# MAIN.net
KiCad netlist of a schematic drawn in Altium Designer
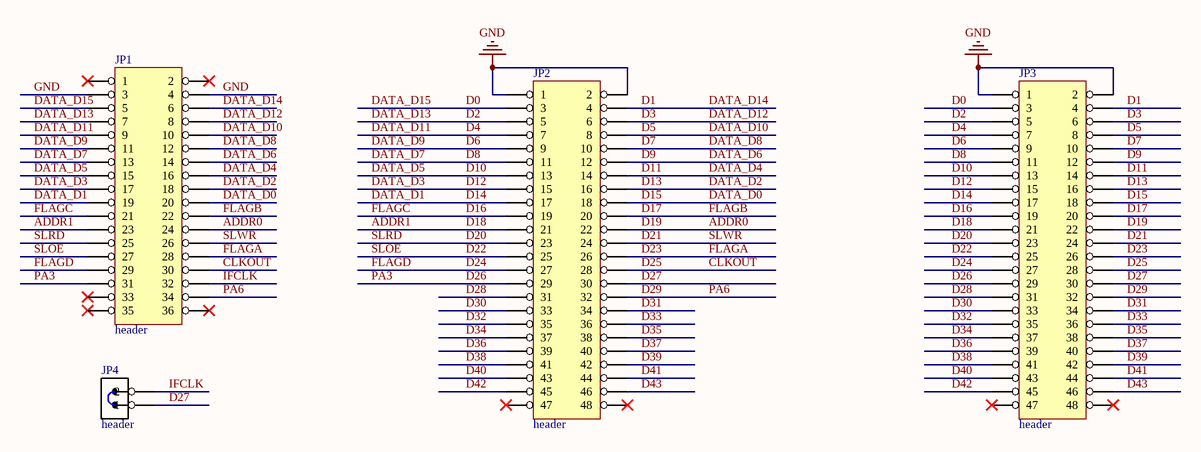
[diagram p0: MAIN.SchDoc]

(export (version "E")
  (design (tool "Eeschema 10.0.6"))
  (components
    (comp (ref "JP1")
      (value "header")
      (footprint "header2X18")
      (libsource (lib "My Footprint") (part "HEADER 18X2"))
    )
    (comp (ref "JP2")
      (value "header")
      (footprint "header2X24")
      (libsource (lib "My Footprint") (part "HEADER 24X2"))
    )
    (comp (ref "JP3")
      (value "header")
      (footprint "header2X24")
      (libsource (lib "My Footprint") (part "HEADER 24X2"))
    )
    (comp (ref "JP4")
      (value "header")
      (footprint "header2")
      (libsource (lib "My Footprint") (part "HEADER 2"))
    )
  )
  (nets
    (net (code "1") (name "/ADDR0") (class "Default")
      (node (ref "JP1") (pin "24") (pinfunction "24_24") (pintype "passive"))
      (node (ref "JP2") (pin "22") (pinfunction "22_22") (pintype "passive"))
      (node (ref "JP3") (pin "22") (pinfunction "22_22") (pintype "passive"))
    )
    (net (code "2") (name "/ADDR1") (class "Default")
      (node (ref "JP1") (pin "23") (pinfunction "23_23") (pintype "passive"))
      (node (ref "JP2") (pin "21") (pinfunction "21_21") (pintype "passive"))
      (node (ref "JP3") (pin "21") (pinfunction "21_21") (pintype "passive"))
    )
    (net (code "3") (name "/CLKOUT") (class "Default")
      (node (ref "JP1") (pin "30") (pinfunction "30_30") (pintype "passive"))
      (node (ref "JP2") (pin "28") (pinfunction "28_28") (pintype "passive"))
      (node (ref "JP3") (pin "28") (pinfunction "28_28") (pintype "passive"))
    )
    (net (code "4") (name "/D0") (class "Default")
      (node (ref "JP1") (pin "5") (pinfunction "5_5") (pintype "passive"))
      (node (ref "JP2") (pin "3") (pinfunction "3_3") (pintype "passive"))
      (node (ref "JP3") (pin "3") (pinfunction "3_3") (pintype "passive"))
    )
    (net (code "5") (name "/D1") (class "Default")
      (node (ref "JP1") (pin "6") (pinfunction "6_6") (pintype "passive"))
      (node (ref "JP2") (pin "4") (pinfunction "4_4") (pintype "passive"))
      (node (ref "JP3") (pin "4") (pinfunction "4_4") (pintype "passive"))
    )
    (net (code "6") (name "/D2") (class "Default")
      (node (ref "JP1") (pin "7") (pinfunction "7_7") (pintype "passive"))
      (node (ref "JP2") (pin "5") (pinfunction "5_5") (pintype "passive"))
      (node (ref "JP3") (pin "5") (pinfunction "5_5") (pintype "passive"))
    )
    (net (code "7") (name "/D3") (class "Default")
      (node (ref "JP1") (pin "8") (pinfunction "8_8") (pintype "passive"))
      (node (ref "JP2") (pin "6") (pinfunction "6_6") (pintype "passive"))
      (node (ref "JP3") (pin "6") (pinfunction "6_6") (pintype "passive"))
    )
    (net (code "8") (name "/D4") (class "Default")
      (node (ref "JP1") (pin "9") (pinfunction "9_9") (pintype "passive"))
      (node (ref "JP2") (pin "7") (pinfunction "7_7") (pintype "passive"))
      (node (ref "JP3") (pin "7") (pinfunction "7_7") (pintype "passive"))
    )
    (net (code "9") (name "/D5") (class "Default")
      (node (ref "JP1") (pin "10") (pinfunction "10_10") (pintype "passive"))
      (node (ref "JP2") (pin "8") (pinfunction "8_8") (pintype "passive"))
      (node (ref "JP3") (pin "8") (pinfunction "8_8") (pintype "passive"))
    )
    (net (code "10") (name "/D6") (class "Default")
      (node (ref "JP1") (pin "11") (pinfunction "11_11") (pintype "passive"))
      (node (ref "JP2") (pin "9") (pinfunction "9_9") (pintype "passive"))
      (node (ref "JP3") (pin "9") (pinfunction "9_9") (pintype "passive"))
    )
    (net (code "11") (name "/D7") (class "Default")
      (node (ref "JP1") (pin "12") (pinfunction "12_12") (pintype "passive"))
      (node (ref "JP2") (pin "10") (pinfunction "10_10") (pintype "passive"))
      (node (ref "JP3") (pin "10") (pinfunction "10_10") (pintype "passive"))
    )
    (net (code "12") (name "/D8") (class "Default")
      (node (ref "JP1") (pin "13") (pinfunction "13_13") (pintype "passive"))
      (node (ref "JP2") (pin "11") (pinfunction "11_11") (pintype "passive"))
      (node (ref "JP3") (pin "11") (pinfunction "11_11") (pintype "passive"))
    )
    (net (code "13") (name "/D9") (class "Default")
      (node (ref "JP1") (pin "14") (pinfunction "14_14") (pintype "passive"))
      (node (ref "JP2") (pin "12") (pinfunction "12_12") (pintype "passive"))
      (node (ref "JP3") (pin "12") (pinfunction "12_12") (pintype "passive"))
    )
    (net (code "14") (name "/D10") (class "Default")
      (node (ref "JP1") (pin "15") (pinfunction "15_15") (pintype "passive"))
      (node (ref "JP2") (pin "13") (pinfunction "13_13") (pintype "passive"))
      (node (ref "JP3") (pin "13") (pinfunction "13_13") (pintype "passive"))
    )
    (net (code "15") (name "/D11") (class "Default")
      (node (ref "JP1") (pin "16") (pinfunction "16_16") (pintype "passive"))
      (node (ref "JP2") (pin "14") (pinfunction "14_14") (pintype "passive"))
      (node (ref "JP3") (pin "14") (pinfunction "14_14") (pintype "passive"))
    )
    (net (code "16") (name "/D12") (class "Default")
      (node (ref "JP1") (pin "17") (pinfunction "17_17") (pintype "passive"))
      (node (ref "JP2") (pin "15") (pinfunction "15_15") (pintype "passive"))
      (node (ref "JP3") (pin "15") (pinfunction "15_15") (pintype "passive"))
    )
    (net (code "17") (name "/D13") (class "Default")
      (node (ref "JP1") (pin "18") (pinfunction "18_18") (pintype "passive"))
      (node (ref "JP2") (pin "16") (pinfunction "16_16") (pintype "passive"))
      (node (ref "JP3") (pin "16") (pinfunction "16_16") (pintype "passive"))
    )
    (net (code "18") (name "/D14") (class "Default")
      (node (ref "JP1") (pin "19") (pinfunction "19_19") (pintype "passive"))
      (node (ref "JP2") (pin "17") (pinfunction "17_17") (pintype "passive"))
      (node (ref "JP3") (pin "17") (pinfunction "17_17") (pintype "passive"))
    )
    (net (code "19") (name "/D15") (class "Default")
      (node (ref "JP1") (pin "20") (pinfunction "20_20") (pintype "passive"))
      (node (ref "JP2") (pin "18") (pinfunction "18_18") (pintype "passive"))
      (node (ref "JP3") (pin "18") (pinfunction "18_18") (pintype "passive"))
    )
    (net (code "20") (name "/D16") (class "Default")
      (node (ref "JP1") (pin "21") (pinfunction "21_21") (pintype "passive"))
      (node (ref "JP2") (pin "19") (pinfunction "19_19") (pintype "passive"))
      (node (ref "JP3") (pin "19") (pinfunction "19_19") (pintype "passive"))
    )
    (net (code "21") (name "/D17") (class "Default")
      (node (ref "JP1") (pin "22") (pinfunction "22_22") (pintype "passive"))
      (node (ref "JP2") (pin "20") (pinfunction "20_20") (pintype "passive"))
      (node (ref "JP3") (pin "20") (pinfunction "20_20") (pintype "passive"))
    )
    (net (code "22") (name "/D20") (class "Default")
      (node (ref "JP1") (pin "25") (pinfunction "25_25") (pintype "passive"))
      (node (ref "JP2") (pin "23") (pinfunction "23_23") (pintype "passive"))
      (node (ref "JP3") (pin "23") (pinfunction "23_23") (pintype "passive"))
    )
    (net (code "23") (name "/D21") (class "Default")
      (node (ref "JP1") (pin "26") (pinfunction "26_26") (pintype "passive"))
      (node (ref "JP2") (pin "24") (pinfunction "24_24") (pintype "passive"))
      (node (ref "JP3") (pin "24") (pinfunction "24_24") (pintype "passive"))
    )
    (net (code "24") (name "/D22") (class "Default")
      (node (ref "JP1") (pin "27") (pinfunction "27_27") (pintype "passive"))
      (node (ref "JP2") (pin "25") (pinfunction "25_25") (pintype "passive"))
      (node (ref "JP3") (pin "25") (pinfunction "25_25") (pintype "passive"))
    )
    (net (code "25") (name "/D23") (class "Default")
      (node (ref "JP1") (pin "28") (pinfunction "28_28") (pintype "passive"))
      (node (ref "JP2") (pin "26") (pinfunction "26_26") (pintype "passive"))
      (node (ref "JP3") (pin "26") (pinfunction "26_26") (pintype "passive"))
    )
    (net (code "26") (name "/D24") (class "Default")
      (node (ref "JP1") (pin "29") (pinfunction "29_29") (pintype "passive"))
      (node (ref "JP2") (pin "27") (pinfunction "27_27") (pintype "passive"))
      (node (ref "JP3") (pin "27") (pinfunction "27_27") (pintype "passive"))
    )
    (net (code "27") (name "/D26") (class "Default")
      (node (ref "JP1") (pin "31") (pinfunction "31_31") (pintype "passive"))
      (node (ref "JP2") (pin "29") (pinfunction "29_29") (pintype "passive"))
      (node (ref "JP3") (pin "29") (pinfunction "29_29") (pintype "passive"))
    )
    (net (code "28") (name "/D27") (class "Default")
      (node (ref "JP2") (pin "30") (pinfunction "30_30") (pintype "passive"))
      (node (ref "JP3") (pin "30") (pinfunction "30_30") (pintype "passive"))
      (node (ref "JP4") (pin "1") (pinfunction "1_1") (pintype "passive"))
    )
    (net (code "29") (name "/D28") (class "Default")
      (node (ref "JP2") (pin "31") (pinfunction "31_31") (pintype "passive"))
      (node (ref "JP3") (pin "31") (pinfunction "31_31") (pintype "passive"))
    )
    (net (code "30") (name "/D29") (class "Default")
      (node (ref "JP1") (pin "34") (pinfunction "34_34") (pintype "passive"))
      (node (ref "JP2") (pin "32") (pinfunction "32_32") (pintype "passive"))
      (node (ref "JP3") (pin "32") (pinfunction "32_32") (pintype "passive"))
    )
    (net (code "31") (name "/D30") (class "Default")
      (node (ref "JP2") (pin "33") (pinfunction "33_33") (pintype "passive"))
      (node (ref "JP3") (pin "33") (pinfunction "33_33") (pintype "passive"))
    )
    (net (code "32") (name "/D31") (class "Default")
      (node (ref "JP2") (pin "34") (pinfunction "34_34") (pintype "passive"))
      (node (ref "JP3") (pin "34") (pinfunction "34_34") (pintype "passive"))
    )
    (net (code "33") (name "/D32") (class "Default")
      (node (ref "JP2") (pin "35") (pinfunction "35_35") (pintype "passive"))
      (node (ref "JP3") (pin "35") (pinfunction "35_35") (pintype "passive"))
    )
    (net (code "34") (name "/D33") (class "Default")
      (node (ref "JP2") (pin "36") (pinfunction "36_36") (pintype "passive"))
      (node (ref "JP3") (pin "36") (pinfunction "36_36") (pintype "passive"))
    )
    (net (code "35") (name "/D34") (class "Default")
      (node (ref "JP2") (pin "37") (pinfunction "37_37") (pintype "passive"))
      (node (ref "JP3") (pin "37") (pinfunction "37_37") (pintype "passive"))
    )
    (net (code "36") (name "/D35") (class "Default")
      (node (ref "JP2") (pin "38") (pinfunction "38_38") (pintype "passive"))
      (node (ref "JP3") (pin "38") (pinfunction "38_38") (pintype "passive"))
    )
    (net (code "37") (name "/D36") (class "Default")
      (node (ref "JP2") (pin "39") (pinfunction "39_39") (pintype "passive"))
      (node (ref "JP3") (pin "39") (pinfunction "39_39") (pintype "passive"))
    )
    (net (code "38") (name "/D37") (class "Default")
      (node (ref "JP2") (pin "40") (pinfunction "40_40") (pintype "passive"))
      (node (ref "JP3") (pin "40") (pinfunction "40_40") (pintype "passive"))
    )
    (net (code "39") (name "/D38") (class "Default")
      (node (ref "JP2") (pin "41") (pinfunction "41_41") (pintype "passive"))
      (node (ref "JP3") (pin "41") (pinfunction "41_41") (pintype "passive"))
    )
    (net (code "40") (name "/D39") (class "Default")
      (node (ref "JP2") (pin "42") (pinfunction "42_42") (pintype "passive"))
      (node (ref "JP3") (pin "42") (pinfunction "42_42") (pintype "passive"))
    )
    (net (code "41") (name "/D40") (class "Default")
      (node (ref "JP2") (pin "43") (pinfunction "43_43") (pintype "passive"))
      (node (ref "JP3") (pin "43") (pinfunction "43_43") (pintype "passive"))
    )
    (net (code "42") (name "/D41") (class "Default")
      (node (ref "JP2") (pin "44") (pinfunction "44_44") (pintype "passive"))
      (node (ref "JP3") (pin "44") (pinfunction "44_44") (pintype "passive"))
    )
    (net (code "43") (name "/D42") (class "Default")
      (node (ref "JP2") (pin "45") (pinfunction "45_45") (pintype "passive"))
      (node (ref "JP3") (pin "45") (pinfunction "45_45") (pintype "passive"))
    )
    (net (code "44") (name "/D43") (class "Default")
      (node (ref "JP2") (pin "46") (pinfunction "46_46") (pintype "passive"))
      (node (ref "JP3") (pin "46") (pinfunction "46_46") (pintype "passive"))
    )
    (net (code "45") (name "/IFCLK") (class "Default")
      (node (ref "JP1") (pin "32") (pinfunction "32_32") (pintype "passive"))
      (node (ref "JP4") (pin "2") (pinfunction "2_2") (pintype "passive"))
    )
    (net (code "46") (name "GND") (class "Default")
      (node (ref "JP1") (pin "3") (pinfunction "3_3") (pintype "passive"))
      (node (ref "JP1") (pin "4") (pinfunction "4_4") (pintype "passive"))
      (node (ref "JP2") (pin "1") (pinfunction "1_1") (pintype "passive"))
      (node (ref "JP2") (pin "2") (pinfunction "2_2") (pintype "passive"))
      (node (ref "JP3") (pin "1") (pinfunction "1_1") (pintype "passive"))
      (node (ref "JP3") (pin "2") (pinfunction "2_2") (pintype "passive"))
    )
    (net (code "47") (name "unconnected-(JP1-Pad1)") (class "Default")
      (node (ref "JP1") (pin "1") (pinfunction "1_1") (pintype "passive+no_connect"))
    )
    (net (code "48") (name "unconnected-(JP1-Pad2)") (class "Default")
      (node (ref "JP1") (pin "2") (pinfunction "2_2") (pintype "passive+no_connect"))
    )
    (net (code "49") (name "unconnected-(JP1-Pad33)") (class "Default")
      (node (ref "JP1") (pin "33") (pinfunction "33_33") (pintype "passive+no_connect"))
    )
    (net (code "50") (name "unconnected-(JP1-Pad35)") (class "Default")
      (node (ref "JP1") (pin "35") (pinfunction "35_35") (pintype "passive+no_connect"))
    )
    (net (code "51") (name "unconnected-(JP1-Pad36)") (class "Default")
      (node (ref "JP1") (pin "36") (pinfunction "36_36") (pintype "passive+no_connect"))
    )
    (net (code "52") (name "unconnected-(JP2-Pad47)") (class "Default")
      (node (ref "JP2") (pin "47") (pinfunction "47_47") (pintype "passive+no_connect"))
    )
    (net (code "53") (name "unconnected-(JP2-Pad48)") (class "Default")
      (node (ref "JP2") (pin "48") (pinfunction "48_48") (pintype "passive+no_connect"))
    )
    (net (code "54") (name "unconnected-(JP3-Pad47)") (class "Default")
      (node (ref "JP3") (pin "47") (pinfunction "47_47") (pintype "passive+no_connect"))
    )
    (net (code "55") (name "unconnected-(JP3-Pad48)") (class "Default")
      (node (ref "JP3") (pin "48") (pinfunction "48_48") (pintype "passive+no_connect"))
    )
  )
)
